# BRK7010.net
KiCad netlist of a schematic drawn in Altium Designer
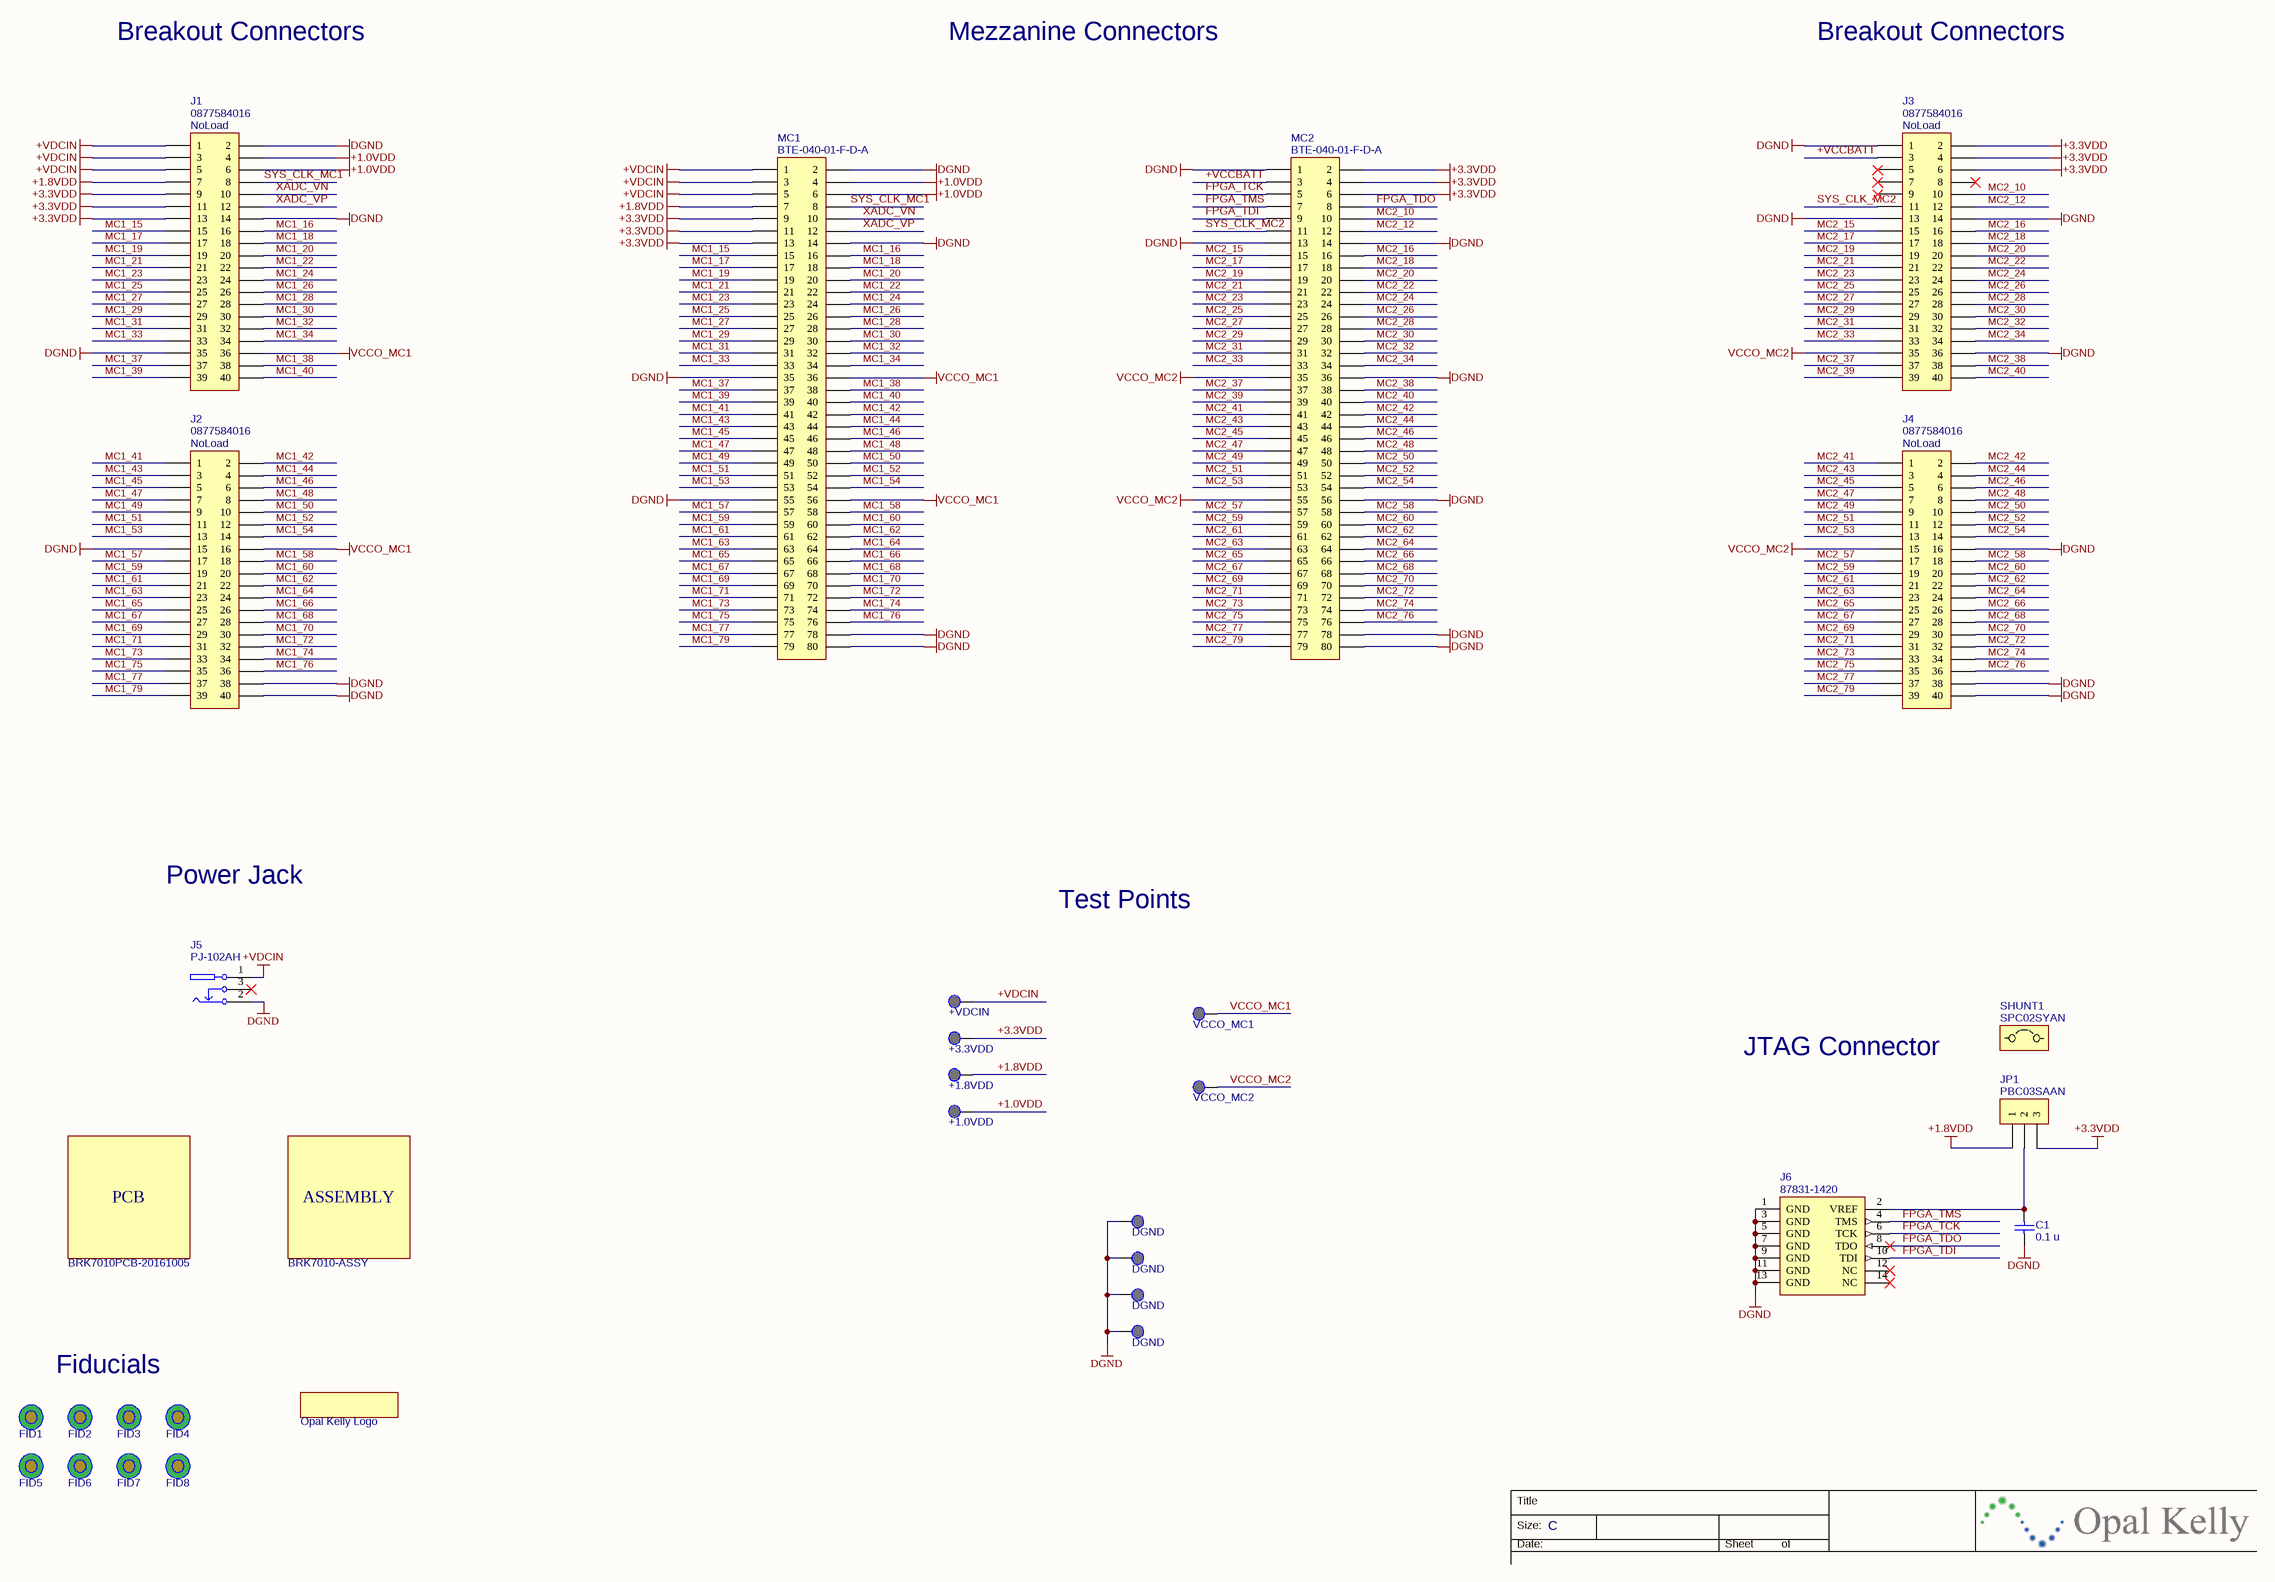
[diagram p0: BRK7010.SchDoc]

(export (version "E")
  (design (tool "Eeschema 10.0.6"))
  (components
    (comp (ref "*1")
      (value "Opal Kelly Logo")
      (footprint "okLogo-23x5")
      (libsource (lib "NoBOM") (part "OKLOGO"))
    )
    (comp (ref "ASSY1")
      (value "BRK7010-ASSY")
      (description "BRK7010 PCB assembly")
      (fields (field (name "MANUFACTURER") "PCB Assembly Cost") (field (name "PARTNUMBER") "001451"))
      (libsource (lib "Aligni") (part "ASSEMBLY"))
    )
    (comp (ref "C1")
      (value "0.1 u")
      (footprint "CAPC1608N")
      (description "Ceramic capacitor")
      (fields (field (name "MANUFACTURER") "Kemet") (field (name "PARTNUMBER") "000019"))
      (libsource (lib "Aligni") (part "Capacitor"))
    )
    (comp (ref "FID1")
      (value "FIDUCIAL")
      (footprint "FID1MM/2MM-SS")
      (description "PCB fiducial")
      (libsource (lib "NoBOM") (part "FIDUCIAL"))
    )
    (comp (ref "FID2")
      (value "FIDUCIAL")
      (footprint "FID1MM/2MM-SS")
      (description "PCB fiducial")
      (libsource (lib "NoBOM") (part "FIDUCIAL"))
    )
    (comp (ref "FID3")
      (value "FIDUCIAL")
      (footprint "FID1MM/2MM-SS")
      (description "PCB fiducial")
      (libsource (lib "NoBOM") (part "FIDUCIAL"))
    )
    (comp (ref "FID4")
      (value "FIDUCIAL")
      (footprint "FID1MM/2MM-SS")
      (description "PCB fiducial")
      (libsource (lib "NoBOM") (part "FIDUCIAL"))
    )
    (comp (ref "FID5")
      (value "FIDUCIAL")
      (footprint "FID1MM/2MM-SS")
      (description "PCB fiducial")
      (libsource (lib "NoBOM") (part "FIDUCIAL"))
    )
    (comp (ref "FID6")
      (value "FIDUCIAL")
      (footprint "FID1MM/2MM-SS")
      (description "PCB fiducial")
      (libsource (lib "NoBOM") (part "FIDUCIAL"))
    )
    (comp (ref "FID7")
      (value "FIDUCIAL")
      (footprint "FID1MM/2MM-SS")
      (description "PCB fiducial")
      (libsource (lib "NoBOM") (part "FIDUCIAL"))
    )
    (comp (ref "FID8")
      (value "FIDUCIAL")
      (footprint "FID1MM/2MM-SS")
      (description "PCB fiducial")
      (libsource (lib "NoBOM") (part "FIDUCIAL"))
    )
    (comp (ref "J1")
      (value "0877584016")
      (footprint "HDR2X20-2MM")
      (description "2mm header, 20x2, thru-hole")
      (fields
        (field (name "MANUFACTURER") "Molex")
        (field (name "PARTNUMBER") "000583")
        (field (name "NOLOAD") "NoLoad")
      )
      (libsource (lib "Aligni") (part "Header 20X2"))
    )
    (comp (ref "J2")
      (value "0877584016")
      (footprint "HDR2X20-2MM")
      (description "2mm header, 20x2, thru-hole")
      (fields
        (field (name "MANUFACTURER") "Molex")
        (field (name "PARTNUMBER") "000583")
        (field (name "NOLOAD") "NoLoad")
      )
      (libsource (lib "Aligni") (part "Header 20X2"))
    )
    (comp (ref "J3")
      (value "0877584016")
      (footprint "HDR2X20-2MM")
      (description "2mm header, 20x2, thru-hole")
      (fields
        (field (name "MANUFACTURER") "Molex")
        (field (name "PARTNUMBER") "000583")
        (field (name "NOLOAD") "NoLoad")
      )
      (libsource (lib "Aligni") (part "Header 20X2"))
    )
    (comp (ref "J4")
      (value "0877584016")
      (footprint "HDR2X20-2MM")
      (description "2mm header, 20x2, thru-hole")
      (fields
        (field (name "MANUFACTURER") "Molex")
        (field (name "PARTNUMBER") "000583")
        (field (name "NOLOAD") "NoLoad")
      )
      (libsource (lib "Aligni") (part "Header 20X2"))
    )
    (comp (ref "J5")
      (value "PJ-102AH")
      (footprint "CUI-PJ102A")
      (description "DC power connector - high current")
      (fields (field (name "MANUFACTURER") "CUI Inc.") (field (name "PARTNUMBER") "000356"))
      (libsource (lib "Aligni") (part "DCPOWER"))
    )
    (comp (ref "J6")
      (value "87831-1420")
      (footprint "HDR2X7-2MM")
      (description "2mm header, shrouded")
      (fields (field (name "MANUFACTURER") "Molex") (field (name "PARTNUMBER") "000541"))
      (libsource (lib "Aligni") (part "JTAGXLNX"))
    )
    (comp (ref "JP1")
      (value "PBC03SAAN")
      (footprint "HDR1X3")
      (description "Single-row header")
      (fields (field (name "MANUFACTURER") "Sullins Electronics Corp.") (field (name "PARTNUMBER") "001173"))
      (libsource (lib "Aligni") (part "Header 1X3"))
    )
    (comp (ref "MC1")
      (value "BTE-040-01-F-D-A")
      (footprint "BTE-040")
      (description "0.8mm high-density header")
      (fields (field (name "MANUFACTURER") "Samtec") (field (name "PARTNUMBER") "000059"))
      (libsource (lib "Aligni") (part "BTE_BSE-040"))
    )
    (comp (ref "MC2")
      (value "BTE-040-01-F-D-A")
      (footprint "BTE-040")
      (description "0.8mm high-density header")
      (fields (field (name "MANUFACTURER") "Samtec") (field (name "PARTNUMBER") "000059"))
      (libsource (lib "Aligni") (part "BTE_BSE-040"))
    )
    (comp (ref "PCB1")
      (value "BRK7010PCB-20161005")
      (description "PCB for BRK7010")
      (fields (field (name "MANUFACTURER") "Generic PCB Manufacturer") (field (name "PARTNUMBER") "001452"))
      (libsource (lib "Aligni") (part "PCB"))
    )
    (comp (ref "SHUNT1")
      (value "SPC02SYAN")
      (description "0.1\" shunt")
      (fields (field (name "MANUFACTURER") "Sullins Electronics Corp.") (field (name "PARTNUMBER") "000078"))
      (libsource (lib "Aligni") (part "Shunt"))
    )
    (comp (ref "TP1")
      (value "+VDCIN")
      (footprint "TP-PTH-65/100")
      (description "Test point, plated through-hole, 65/100mil")
      (libsource (lib "NoBOM") (part "TP-PTH-65/100"))
    )
    (comp (ref "TP2")
      (value "VCCO_MC1")
      (footprint "TP-PTH-65/100")
      (description "Test point, plated through-hole, 65/100mil")
      (libsource (lib "NoBOM") (part "TP-PTH-65/100"))
    )
    (comp (ref "TP3")
      (value "+3.3VDD")
      (footprint "TP-PTH-65/100")
      (description "Test point, plated through-hole, 65/100mil")
      (libsource (lib "NoBOM") (part "TP-PTH-65/100"))
    )
    (comp (ref "TP4")
      (value "+1.8VDD")
      (footprint "TP-PTH-65/100")
      (description "Test point, plated through-hole, 65/100mil")
      (libsource (lib "NoBOM") (part "TP-PTH-65/100"))
    )
    (comp (ref "TP5")
      (value "VCCO_MC2")
      (footprint "TP-PTH-65/100")
      (description "Test point, plated through-hole, 65/100mil")
      (libsource (lib "NoBOM") (part "TP-PTH-65/100"))
    )
    (comp (ref "TP6")
      (value "+1.0VDD")
      (footprint "TP-PTH-65/100")
      (description "Test point, plated through-hole, 65/100mil")
      (libsource (lib "NoBOM") (part "TP-PTH-65/100"))
    )
    (comp (ref "TP7")
      (value "DGND")
      (footprint "TP-PTH-65/100")
      (description "Test point, plated through-hole, 65/100mil")
      (libsource (lib "NoBOM") (part "TP-PTH-65/100"))
    )
    (comp (ref "TP8")
      (value "DGND")
      (footprint "TP-PTH-65/100")
      (description "Test point, plated through-hole, 65/100mil")
      (libsource (lib "NoBOM") (part "TP-PTH-65/100"))
    )
    (comp (ref "TP9")
      (value "DGND")
      (footprint "TP-PTH-65/100")
      (description "Test point, plated through-hole, 65/100mil")
      (libsource (lib "NoBOM") (part "TP-PTH-65/100"))
    )
    (comp (ref "TP10")
      (value "DGND")
      (footprint "TP-PTH-65/100")
      (description "Test point, plated through-hole, 65/100mil")
      (libsource (lib "NoBOM") (part "TP-PTH-65/100"))
    )
  )
  (nets
    (net (code "1") (name "+1.0VDD") (class "Default")
      (node (ref "J1") (pin "4") (pinfunction "4_4") (pintype "passive"))
      (node (ref "J1") (pin "6") (pinfunction "6_6") (pintype "passive"))
      (node (ref "MC1") (pin "4") (pinfunction "4_4") (pintype "passive"))
      (node (ref "MC1") (pin "6") (pinfunction "6_6") (pintype "passive"))
      (node (ref "TP6") (pin "1") (pinfunction "PIN_1") (pintype "passive"))
    )
    (net (code "2") (name "+1.8VDD") (class "Default")
      (node (ref "J1") (pin "7") (pinfunction "7_7") (pintype "passive"))
      (node (ref "JP1") (pin "1") (pinfunction "1_1") (pintype "passive"))
      (node (ref "MC1") (pin "7") (pinfunction "7_7") (pintype "passive"))
      (node (ref "TP4") (pin "1") (pinfunction "PIN_1") (pintype "passive"))
    )
    (net (code "3") (name "+3.3VDD") (class "Default")
      (node (ref "J1") (pin "11") (pinfunction "11_11") (pintype "passive"))
      (node (ref "J1") (pin "13") (pinfunction "13_13") (pintype "passive"))
      (node (ref "J1") (pin "9") (pinfunction "9_9") (pintype "passive"))
      (node (ref "J3") (pin "2") (pinfunction "2_2") (pintype "passive"))
      (node (ref "J3") (pin "4") (pinfunction "4_4") (pintype "passive"))
      (node (ref "J3") (pin "6") (pinfunction "6_6") (pintype "passive"))
      (node (ref "JP1") (pin "3") (pinfunction "3_3") (pintype "passive"))
      (node (ref "MC1") (pin "11") (pinfunction "11_11") (pintype "passive"))
      (node (ref "MC1") (pin "13") (pinfunction "13_13") (pintype "passive"))
      (node (ref "MC1") (pin "9") (pinfunction "9_9") (pintype "passive"))
      (node (ref "MC2") (pin "2") (pinfunction "2_2") (pintype "passive"))
      (node (ref "MC2") (pin "4") (pinfunction "4_4") (pintype "passive"))
      (node (ref "MC2") (pin "6") (pinfunction "6_6") (pintype "passive"))
      (node (ref "TP3") (pin "1") (pinfunction "PIN_1") (pintype "passive"))
    )
    (net (code "4") (name "+VDCIN") (class "Default")
      (node (ref "J1") (pin "1") (pinfunction "1_1") (pintype "passive"))
      (node (ref "J1") (pin "3") (pinfunction "3_3") (pintype "passive"))
      (node (ref "J1") (pin "5") (pinfunction "5_5") (pintype "passive"))
      (node (ref "J5") (pin "1") (pinfunction "1_1") (pintype "passive"))
      (node (ref "MC1") (pin "1") (pinfunction "1_1") (pintype "passive"))
      (node (ref "MC1") (pin "3") (pinfunction "3_3") (pintype "passive"))
      (node (ref "MC1") (pin "5") (pinfunction "5_5") (pintype "passive"))
      (node (ref "TP1") (pin "1") (pinfunction "PIN_1") (pintype "passive"))
    )
    (net (code "5") (name "/+VCCBATT") (class "Default")
      (node (ref "J3") (pin "3") (pinfunction "3_3") (pintype "passive"))
      (node (ref "MC2") (pin "3") (pinfunction "3_3") (pintype "passive"))
    )
    (net (code "6") (name "/FPGA_TCK") (class "Default")
      (node (ref "J6") (pin "6") (pinfunction "TCK_6") (pintype "output"))
      (node (ref "MC2") (pin "5") (pinfunction "5_5") (pintype "passive"))
    )
    (net (code "7") (name "/FPGA_TDI") (class "Default")
      (node (ref "J6") (pin "10") (pinfunction "TDI_10") (pintype "output"))
      (node (ref "MC2") (pin "9") (pinfunction "9_9") (pintype "passive"))
    )
    (net (code "8") (name "/FPGA_TDO") (class "Default")
      (node (ref "J6") (pin "8") (pinfunction "TDO_8") (pintype "input"))
      (node (ref "MC2") (pin "8") (pinfunction "8_8") (pintype "passive"))
    )
    (net (code "9") (name "/FPGA_TMS") (class "Default")
      (node (ref "J6") (pin "4") (pinfunction "TMS_4") (pintype "output"))
      (node (ref "MC2") (pin "7") (pinfunction "7_7") (pintype "passive"))
    )
    (net (code "10") (name "/MC1_15") (class "Default")
      (node (ref "J1") (pin "15") (pinfunction "15_15") (pintype "passive"))
      (node (ref "MC1") (pin "15") (pinfunction "15_15") (pintype "passive"))
    )
    (net (code "11") (name "/MC1_16") (class "Default")
      (node (ref "J1") (pin "16") (pinfunction "16_16") (pintype "passive"))
      (node (ref "MC1") (pin "16") (pinfunction "16_16") (pintype "passive"))
    )
    (net (code "12") (name "/MC1_17") (class "Default")
      (node (ref "J1") (pin "17") (pinfunction "17_17") (pintype "passive"))
      (node (ref "MC1") (pin "17") (pinfunction "17_17") (pintype "passive"))
    )
    (net (code "13") (name "/MC1_18") (class "Default")
      (node (ref "J1") (pin "18") (pinfunction "18_18") (pintype "passive"))
      (node (ref "MC1") (pin "18") (pinfunction "18_18") (pintype "passive"))
    )
    (net (code "14") (name "/MC1_19") (class "Default")
      (node (ref "J1") (pin "19") (pinfunction "19_19") (pintype "passive"))
      (node (ref "MC1") (pin "19") (pinfunction "19_19") (pintype "passive"))
    )
    (net (code "15") (name "/MC1_20") (class "Default")
      (node (ref "J1") (pin "20") (pinfunction "20_20") (pintype "passive"))
      (node (ref "MC1") (pin "20") (pinfunction "20_20") (pintype "passive"))
    )
    (net (code "16") (name "/MC1_21") (class "Default")
      (node (ref "J1") (pin "21") (pinfunction "21_21") (pintype "passive"))
      (node (ref "MC1") (pin "21") (pinfunction "21_21") (pintype "passive"))
    )
    (net (code "17") (name "/MC1_22") (class "Default")
      (node (ref "J1") (pin "22") (pinfunction "22_22") (pintype "passive"))
      (node (ref "MC1") (pin "22") (pinfunction "22_22") (pintype "passive"))
    )
    (net (code "18") (name "/MC1_23") (class "Default")
      (node (ref "J1") (pin "23") (pinfunction "23_23") (pintype "passive"))
      (node (ref "MC1") (pin "23") (pinfunction "23_23") (pintype "passive"))
    )
    (net (code "19") (name "/MC1_24") (class "Default")
      (node (ref "J1") (pin "24") (pinfunction "24_24") (pintype "passive"))
      (node (ref "MC1") (pin "24") (pinfunction "24_24") (pintype "passive"))
    )
    (net (code "20") (name "/MC1_25") (class "Default")
      (node (ref "J1") (pin "25") (pinfunction "25_25") (pintype "passive"))
      (node (ref "MC1") (pin "25") (pinfunction "25_25") (pintype "passive"))
    )
    (net (code "21") (name "/MC1_26") (class "Default")
      (node (ref "J1") (pin "26") (pinfunction "26_26") (pintype "passive"))
      (node (ref "MC1") (pin "26") (pinfunction "26_26") (pintype "passive"))
    )
    (net (code "22") (name "/MC1_27") (class "Default")
      (node (ref "J1") (pin "27") (pinfunction "27_27") (pintype "passive"))
      (node (ref "MC1") (pin "27") (pinfunction "27_27") (pintype "passive"))
    )
    (net (code "23") (name "/MC1_28") (class "Default")
      (node (ref "J1") (pin "28") (pinfunction "28_28") (pintype "passive"))
      (node (ref "MC1") (pin "28") (pinfunction "28_28") (pintype "passive"))
    )
    (net (code "24") (name "/MC1_29") (class "Default")
      (node (ref "J1") (pin "29") (pinfunction "29_29") (pintype "passive"))
      (node (ref "MC1") (pin "29") (pinfunction "29_29") (pintype "passive"))
    )
    (net (code "25") (name "/MC1_30") (class "Default")
      (node (ref "J1") (pin "30") (pinfunction "30_30") (pintype "passive"))
      (node (ref "MC1") (pin "30") (pinfunction "30_30") (pintype "passive"))
    )
    (net (code "26") (name "/MC1_31") (class "Default")
      (node (ref "J1") (pin "31") (pinfunction "31_31") (pintype "passive"))
      (node (ref "MC1") (pin "31") (pinfunction "31_31") (pintype "passive"))
    )
    (net (code "27") (name "/MC1_32") (class "Default")
      (node (ref "J1") (pin "32") (pinfunction "32_32") (pintype "passive"))
      (node (ref "MC1") (pin "32") (pinfunction "32_32") (pintype "passive"))
    )
    (net (code "28") (name "/MC1_33") (class "Default")
      (node (ref "J1") (pin "33") (pinfunction "33_33") (pintype "passive"))
      (node (ref "MC1") (pin "33") (pinfunction "33_33") (pintype "passive"))
    )
    (net (code "29") (name "/MC1_34") (class "Default")
      (node (ref "J1") (pin "34") (pinfunction "34_34") (pintype "passive"))
      (node (ref "MC1") (pin "34") (pinfunction "34_34") (pintype "passive"))
    )
    (net (code "30") (name "/MC1_37") (class "Default")
      (node (ref "J1") (pin "37") (pinfunction "37_37") (pintype "passive"))
      (node (ref "MC1") (pin "37") (pinfunction "37_37") (pintype "passive"))
    )
    (net (code "31") (name "/MC1_38") (class "Default")
      (node (ref "J1") (pin "38") (pinfunction "38_38") (pintype "passive"))
      (node (ref "MC1") (pin "38") (pinfunction "38_38") (pintype "passive"))
    )
    (net (code "32") (name "/MC1_39") (class "Default")
      (node (ref "J1") (pin "39") (pinfunction "39_39") (pintype "passive"))
      (node (ref "MC1") (pin "39") (pinfunction "39_39") (pintype "passive"))
    )
    (net (code "33") (name "/MC1_40") (class "Default")
      (node (ref "J1") (pin "40") (pinfunction "40_40") (pintype "passive"))
      (node (ref "MC1") (pin "40") (pinfunction "40_40") (pintype "passive"))
    )
    (net (code "34") (name "/MC1_41") (class "Default")
      (node (ref "J2") (pin "1") (pinfunction "1_1") (pintype "passive"))
      (node (ref "MC1") (pin "41") (pinfunction "41_41") (pintype "passive"))
    )
    (net (code "35") (name "/MC1_42") (class "Default")
      (node (ref "J2") (pin "2") (pinfunction "2_2") (pintype "passive"))
      (node (ref "MC1") (pin "42") (pinfunction "42_42") (pintype "passive"))
    )
    (net (code "36") (name "/MC1_43") (class "Default")
      (node (ref "J2") (pin "3") (pinfunction "3_3") (pintype "passive"))
      (node (ref "MC1") (pin "43") (pinfunction "43_43") (pintype "passive"))
    )
    (net (code "37") (name "/MC1_44") (class "Default")
      (node (ref "J2") (pin "4") (pinfunction "4_4") (pintype "passive"))
      (node (ref "MC1") (pin "44") (pinfunction "44_44") (pintype "passive"))
    )
    (net (code "38") (name "/MC1_45") (class "Default")
      (node (ref "J2") (pin "5") (pinfunction "5_5") (pintype "passive"))
      (node (ref "MC1") (pin "45") (pinfunction "45_45") (pintype "passive"))
    )
    (net (code "39") (name "/MC1_46") (class "Default")
      (node (ref "J2") (pin "6") (pinfunction "6_6") (pintype "passive"))
      (node (ref "MC1") (pin "46") (pinfunction "46_46") (pintype "passive"))
    )
    (net (code "40") (name "/MC1_47") (class "Default")
      (node (ref "J2") (pin "7") (pinfunction "7_7") (pintype "passive"))
      (node (ref "MC1") (pin "47") (pinfunction "47_47") (pintype "passive"))
    )
    (net (code "41") (name "/MC1_48") (class "Default")
      (node (ref "J2") (pin "8") (pinfunction "8_8") (pintype "passive"))
      (node (ref "MC1") (pin "48") (pinfunction "48_48") (pintype "passive"))
    )
    (net (code "42") (name "/MC1_49") (class "Default")
      (node (ref "J2") (pin "9") (pinfunction "9_9") (pintype "passive"))
      (node (ref "MC1") (pin "49") (pinfunction "49_49") (pintype "passive"))
    )
    (net (code "43") (name "/MC1_50") (class "Default")
      (node (ref "J2") (pin "10") (pinfunction "10_10") (pintype "passive"))
      (node (ref "MC1") (pin "50") (pinfunction "50_50") (pintype "passive"))
    )
    (net (code "44") (name "/MC1_51") (class "Default")
      (node (ref "J2") (pin "11") (pinfunction "11_11") (pintype "passive"))
      (node (ref "MC1") (pin "51") (pinfunction "51_51") (pintype "passive"))
    )
    (net (code "45") (name "/MC1_52") (class "Default")
      (node (ref "J2") (pin "12") (pinfunction "12_12") (pintype "passive"))
      (node (ref "MC1") (pin "52") (pinfunction "52_52") (pintype "passive"))
    )
    (net (code "46") (name "/MC1_53") (class "Default")
      (node (ref "J2") (pin "13") (pinfunction "13_13") (pintype "passive"))
      (node (ref "MC1") (pin "53") (pinfunction "53_53") (pintype "passive"))
    )
    (net (code "47") (name "/MC1_54") (class "Default")
      (node (ref "J2") (pin "14") (pinfunction "14_14") (pintype "passive"))
      (node (ref "MC1") (pin "54") (pinfunction "54_54") (pintype "passive"))
    )
    (net (code "48") (name "/MC1_57") (class "Default")
      (node (ref "J2") (pin "17") (pinfunction "17_17") (pintype "passive"))
      (node (ref "MC1") (pin "57") (pinfunction "57_57") (pintype "passive"))
    )
    (net (code "49") (name "/MC1_58") (class "Default")
      (node (ref "J2") (pin "18") (pinfunction "18_18") (pintype "passive"))
      (node (ref "MC1") (pin "58") (pinfunction "58_58") (pintype "passive"))
    )
    (net (code "50") (name "/MC1_59") (class "Default")
      (node (ref "J2") (pin "19") (pinfunction "19_19") (pintype "passive"))
      (node (ref "MC1") (pin "59") (pinfunction "59_59") (pintype "passive"))
    )
    (net (code "51") (name "/MC1_60") (class "Default")
      (node (ref "J2") (pin "20") (pinfunction "20_20") (pintype "passive"))
      (node (ref "MC1") (pin "60") (pinfunction "60_60") (pintype "passive"))
    )
    (net (code "52") (name "/MC1_61") (class "Default")
      (node (ref "J2") (pin "21") (pinfunction "21_21") (pintype "passive"))
      (node (ref "MC1") (pin "61") (pinfunction "61_61") (pintype "passive"))
    )
    (net (code "53") (name "/MC1_62") (class "Default")
      (node (ref "J2") (pin "22") (pinfunction "22_22") (pintype "passive"))
      (node (ref "MC1") (pin "62") (pinfunction "62_62") (pintype "passive"))
    )
    (net (code "54") (name "/MC1_63") (class "Default")
      (node (ref "J2") (pin "23") (pinfunction "23_23") (pintype "passive"))
      (node (ref "MC1") (pin "63") (pinfunction "63_63") (pintype "passive"))
    )
    (net (code "55") (name "/MC1_64") (class "Default")
      (node (ref "J2") (pin "24") (pinfunction "24_24") (pintype "passive"))
      (node (ref "MC1") (pin "64") (pinfunction "64_64") (pintype "passive"))
    )
    (net (code "56") (name "/MC1_65") (class "Default")
      (node (ref "J2") (pin "25") (pinfunction "25_25") (pintype "passive"))
      (node (ref "MC1") (pin "65") (pinfunction "65_65") (pintype "passive"))
    )
    (net (code "57") (name "/MC1_66") (class "Default")
      (node (ref "J2") (pin "26") (pinfunction "26_26") (pintype "passive"))
      (node (ref "MC1") (pin "66") (pinfunction "66_66") (pintype "passive"))
    )
    (net (code "58") (name "/MC1_67") (class "Default")
      (node (ref "J2") (pin "27") (pinfunction "27_27") (pintype "passive"))
      (node (ref "MC1") (pin "67") (pinfunction "67_67") (pintype "passive"))
    )
    (net (code "59") (name "/MC1_68") (class "Default")
      (node (ref "J2") (pin "28") (pinfunction "28_28") (pintype "passive"))
      (node (ref "MC1") (pin "68") (pinfunction "68_68") (pintype "passive"))
    )
    (net (code "60") (name "/MC1_69") (class "Default")
      (node (ref "J2") (pin "29") (pinfunction "29_29") (pintype "passive"))
      (node (ref "MC1") (pin "69") (pinfunction "69_69") (pintype "passive"))
    )
    (net (code "61") (name "/MC1_70") (class "Default")
      (node (ref "J2") (pin "30") (pinfunction "30_30") (pintype "passive"))
      (node (ref "MC1") (pin "70") (pinfunction "70_70") (pintype "passive"))
    )
    (net (code "62") (name "/MC1_71") (class "Default")
      (node (ref "J2") (pin "31") (pinfunction "31_31") (pintype "passive"))
      (node (ref "MC1") (pin "71") (pinfunction "71_71") (pintype "passive"))
    )
    (net (code "63") (name "/MC1_72") (class "Default")
      (node (ref "J2") (pin "32") (pinfunction "32_32") (pintype "passive"))
      (node (ref "MC1") (pin "72") (pinfunction "72_72") (pintype "passive"))
    )
    (net (code "64") (name "/MC1_73") (class "Default")
      (node (ref "J2") (pin "33") (pinfunction "33_33") (pintype "passive"))
      (node (ref "MC1") (pin "73") (pinfunction "73_73") (pintype "passive"))
    )
    (net (code "65") (name "/MC1_74") (class "Default")
      (node (ref "J2") (pin "34") (pinfunction "34_34") (pintype "passive"))
      (node (ref "MC1") (pin "74") (pinfunction "74_74") (pintype "passive"))
    )
    (net (code "66") (name "/MC1_75") (class "Default")
      (node (ref "J2") (pin "35") (pinfunction "35_35") (pintype "passive"))
      (node (ref "MC1") (pin "75") (pinfunction "75_75") (pintype "passive"))
    )
    (net (code "67") (name "/MC1_76") (class "Default")
      (node (ref "J2") (pin "36") (pinfunction "36_36") (pintype "passive"))
      (node (ref "MC1") (pin "76") (pinfunction "76_76") (pintype "passive"))
    )
    (net (code "68") (name "/MC1_77") (class "Default")
      (node (ref "J2") (pin "37") (pinfunction "37_37") (pintype "passive"))
      (node (ref "MC1") (pin "77") (pinfunction "77_77") (pintype "passive"))
    )
    (net (code "69") (name "/MC1_79") (class "Default")
      (node (ref "J2") (pin "39") (pinfunction "39_39") (pintype "passive"))
      (node (ref "MC1") (pin "79") (pinfunction "79_79") (pintype "passive"))
    )
    (net (code "70") (name "/MC2_10") (class "Default")
      (node (ref "J3") (pin "10") (pinfunction "10_10") (pintype "passive"))
      (node (ref "MC2") (pin "10") (pinfunction "10_10") (pintype "passive"))
    )
    (net (code "71") (name "/MC2_12") (class "Default")
      (node (ref "J3") (pin "12") (pinfunction "12_12") (pintype "passive"))
      (node (ref "MC2") (pin "12") (pinfunction "12_12") (pintype "passive"))
    )
    (net (code "72") (name "/MC2_15") (class "Default")
      (node (ref "J3") (pin "15") (pinfunction "15_15") (pintype "passive"))
      (node (ref "MC2") (pin "15") (pinfunction "15_15") (pintype "passive"))
    )
    (net (code "73") (name "/MC2_16") (class "Default")
      (node (ref "J3") (pin "16") (pinfunction "16_16") (pintype "passive"))
      (node (ref "MC2") (pin "16") (pinfunction "16_16") (pintype "passive"))
    )
    (net (code "74") (name "/MC2_17") (class "Default")
      (node (ref "J3") (pin "17") (pinfunction "17_17") (pintype "passive"))
      (node (ref "MC2") (pin "17") (pinfunction "17_17") (pintype "passive"))
    )
    (net (code "75") (name "/MC2_18") (class "Default")
      (node (ref "J3") (pin "18") (pinfunction "18_18") (pintype "passive"))
      (node (ref "MC2") (pin "18") (pinfunction "18_18") (pintype "passive"))
    )
    (net (code "76") (name "/MC2_19") (class "Default")
      (node (ref "J3") (pin "19") (pinfunction "19_19") (pintype "passive"))
      (node (ref "MC2") (pin "19") (pinfunction "19_19") (pintype "passive"))
    )
    (net (code "77") (name "/MC2_20") (class "Default")
      (node (ref "J3") (pin "20") (pinfunction "20_20") (pintype "passive"))
      (node (ref "MC2") (pin "20") (pinfunction "20_20") (pintype "passive"))
    )
    (net (code "78") (name "/MC2_21") (class "Default")
      (node (ref "J3") (pin "21") (pinfunction "21_21") (pintype "passive"))
      (node (ref "MC2") (pin "21") (pinfunction "21_21") (pintype "passive"))
    )
    (net (code "79") (name "/MC2_22") (class "Default")
      (node (ref "J3") (pin "22") (pinfunction "22_22") (pintype "passive"))
      (node (ref "MC2") (pin "22") (pinfunction "22_22") (pintype "passive"))
    )
    (net (code "80") (name "/MC2_23") (class "Default")
      (node (ref "J3") (pin "23") (pinfunction "23_23") (pintype "passive"))
      (node (ref "MC2") (pin "23") (pinfunction "23_23") (pintype "passive"))
    )
    (net (code "81") (name "/MC2_24") (class "Default")
      (node (ref "J3") (pin "24") (pinfunction "24_24") (pintype "passive"))
      (node (ref "MC2") (pin "24") (pinfunction "24_24") (pintype "passive"))
    )
    (net (code "82") (name "/MC2_25") (class "Default")
      (node (ref "J3") (pin "25") (pinfunction "25_25") (pintype "passive"))
      (node (ref "MC2") (pin "25") (pinfunction "25_25") (pintype "passive"))
    )
    (net (code "83") (name "/MC2_26") (class "Default")
      (node (ref "J3") (pin "26") (pinfunction "26_26") (pintype "passive"))
      (node (ref "MC2") (pin "26") (pinfunction "26_26") (pintype "passive"))
    )
    (net (code "84") (name "/MC2_27") (class "Default")
      (node (ref "J3") (pin "27") (pinfunction "27_27") (pintype "passive"))
      (node (ref "MC2") (pin "27") (pinfunction "27_27") (pintype "passive"))
    )
    (net (code "85") (name "/MC2_28") (class "Default")
      (node (ref "J3") (pin "28") (pinfunction "28_28") (pintype "passive"))
      (node (ref "MC2") (pin "28") (pinfunction "28_28") (pintype "passive"))
    )
    (net (code "86") (name "/MC2_29") (class "Default")
      (node (ref "J3") (pin "29") (pinfunction "29_29") (pintype "passive"))
      (node (ref "MC2") (pin "29") (pinfunction "29_29") (pintype "passive"))
    )
    (net (code "87") (name "/MC2_30") (class "Default")
      (node (ref "J3") (pin "30") (pinfunction "30_30") (pintype "passive"))
      (node (ref "MC2") (pin "30") (pinfunction "30_30") (pintype "passive"))
    )
    (net (code "88") (name "/MC2_31") (class "Default")
      (node (ref "J3") (pin "31") (pinfunction "31_31") (pintype "passive"))
      (node (ref "MC2") (pin "31") (pinfunction "31_31") (pintype "passive"))
    )
    (net (code "89") (name "/MC2_32") (class "Default")
      (node (ref "J3") (pin "32") (pinfunction "32_32") (pintype "passive"))
      (node (ref "MC2") (pin "32") (pinfunction "32_32") (pintype "passive"))
    )
    (net (code "90") (name "/MC2_33") (class "Default")
      (node (ref "J3") (pin "33") (pinfunction "33_33") (pintype "passive"))
      (node (ref "MC2") (pin "33") (pinfunction "33_33") (pintype "passive"))
    )
    (net (code "91") (name "/MC2_34") (class "Default")
      (node (ref "J3") (pin "34") (pinfunction "34_34") (pintype "passive"))
      (node (ref "MC2") (pin "34") (pinfunction "34_34") (pintype "passive"))
    )
    (net (code "92") (name "/MC2_37") (class "Default")
      (node (ref "J3") (pin "37") (pinfunction "37_37") (pintype "passive"))
      (node (ref "MC2") (pin "37") (pinfunction "37_37") (pintype "passive"))
    )
    (net (code "93") (name "/MC2_38") (class "Default")
      (node (ref "J3") (pin "38") (pinfunction "38_38") (pintype "passive"))
      (node (ref "MC2") (pin "38") (pinfunction "38_38") (pintype "passive"))
    )
    (net (code "94") (name "/MC2_39") (class "Default")
      (node (ref "J3") (pin "39") (pinfunction "39_39") (pintype "passive"))
      (node (ref "MC2") (pin "39") (pinfunction "39_39") (pintype "passive"))
    )
    (net (code "95") (name "/MC2_40") (class "Default")
      (node (ref "J3") (pin "40") (pinfunction "40_40") (pintype "passive"))
      (node (ref "MC2") (pin "40") (pinfunction "40_40") (pintype "passive"))
    )
    (net (code "96") (name "/MC2_41") (class "Default")
      (node (ref "J4") (pin "1") (pinfunction "1_1") (pintype "passive"))
      (node (ref "MC2") (pin "41") (pinfunction "41_41") (pintype "passive"))
    )
    (net (code "97") (name "/MC2_42") (class "Default")
      (node (ref "J4") (pin "2") (pinfunction "2_2") (pintype "passive"))
      (node (ref "MC2") (pin "42") (pinfunction "42_42") (pintype "passive"))
    )
    (net (code "98") (name "/MC2_43") (class "Default")
      (node (ref "J4") (pin "3") (pinfunction "3_3") (pintype "passive"))
      (node (ref "MC2") (pin "43") (pinfunction "43_43") (pintype "passive"))
    )
    (net (code "99") (name "/MC2_44") (class "Default")
      (node (ref "J4") (pin "4") (pinfunction "4_4") (pintype "passive"))
      (node (ref "MC2") (pin "44") (pinfunction "44_44") (pintype "passive"))
    )
    (net (code "100") (name "/MC2_45") (class "Default")
      (node (ref "J4") (pin "5") (pinfunction "5_5") (pintype "passive"))
      (node (ref "MC2") (pin "45") (pinfunction "45_45") (pintype "passive"))
    )
    (net (code "101") (name "/MC2_46") (class "Default")
      (node (ref "J4") (pin "6") (pinfunction "6_6") (pintype "passive"))
      (node (ref "MC2") (pin "46") (pinfunction "46_46") (pintype "passive"))
    )
    (net (code "102") (name "/MC2_47") (class "Default")
      (node (ref "J4") (pin "7") (pinfunction "7_7") (pintype "passive"))
      (node (ref "MC2") (pin "47") (pinfunction "47_47") (pintype "passive"))
    )
    (net (code "103") (name "/MC2_48") (class "Default")
      (node (ref "J4") (pin "8") (pinfunction "8_8") (pintype "passive"))
      (node (ref "MC2") (pin "48") (pinfunction "48_48") (pintype "passive"))
    )
    (net (code "104") (name "/MC2_49") (class "Default")
      (node (ref "J4") (pin "9") (pinfunction "9_9") (pintype "passive"))
      (node (ref "MC2") (pin "49") (pinfunction "49_49") (pintype "passive"))
    )
    (net (code "105") (name "/MC2_50") (class "Default")
      (node (ref "J4") (pin "10") (pinfunction "10_10") (pintype "passive"))
      (node (ref "MC2") (pin "50") (pinfunction "50_50") (pintype "passive"))
    )
    (net (code "106") (name "/MC2_51") (class "Default")
      (node (ref "J4") (pin "11") (pinfunction "11_11") (pintype "passive"))
      (node (ref "MC2") (pin "51") (pinfunction "51_51") (pintype "passive"))
    )
    (net (code "107") (name "/MC2_52") (class "Default")
      (node (ref "J4") (pin "12") (pinfunction "12_12") (pintype "passive"))
      (node (ref "MC2") (pin "52") (pinfunction "52_52") (pintype "passive"))
    )
    (net (code "108") (name "/MC2_53") (class "Default")
      (node (ref "J4") (pin "13") (pinfunction "13_13") (pintype "passive"))
      (node (ref "MC2") (pin "53") (pinfunction "53_53") (pintype "passive"))
    )
    (net (code "109") (name "/MC2_54") (class "Default")
      (node (ref "J4") (pin "14") (pinfunction "14_14") (pintype "passive"))
      (node (ref "MC2") (pin "54") (pinfunction "54_54") (pintype "passive"))
    )
    (net (code "110") (name "/MC2_57") (class "Default")
      (node (ref "J4") (pin "17") (pinfunction "17_17") (pintype "passive"))
      (node (ref "MC2") (pin "57") (pinfunction "57_57") (pintype "passive"))
    )
    (net (code "111") (name "/MC2_58") (class "Default")
      (node (ref "J4") (pin "18") (pinfunction "18_18") (pintype "passive"))
      (node (ref "MC2") (pin "58") (pinfunction "58_58") (pintype "passive"))
    )
    (net (code "112") (name "/MC2_59") (class "Default")
      (node (ref "J4") (pin "19") (pinfunction "19_19") (pintype "passive"))
      (node (ref "MC2") (pin "59") (pinfunction "59_59") (pintype "passive"))
    )
    (net (code "113") (name "/MC2_60") (class "Default")
      (node (ref "J4") (pin "20") (pinfunction "20_20") (pintype "passive"))
      (node (ref "MC2") (pin "60") (pinfunction "60_60") (pintype "passive"))
    )
    (net (code "114") (name "/MC2_61") (class "Default")
      (node (ref "J4") (pin "21") (pinfunction "21_21") (pintype "passive"))
      (node (ref "MC2") (pin "61") (pinfunction "61_61") (pintype "passive"))
    )
    (net (code "115") (name "/MC2_62") (class "Default")
      (node (ref "J4") (pin "22") (pinfunction "22_22") (pintype "passive"))
      (node (ref "MC2") (pin "62") (pinfunction "62_62") (pintype "passive"))
    )
    (net (code "116") (name "/MC2_63") (class "Default")
      (node (ref "J4") (pin "23") (pinfunction "23_23") (pintype "passive"))
      (node (ref "MC2") (pin "63") (pinfunction "63_63") (pintype "passive"))
    )
    (net (code "117") (name "/MC2_64") (class "Default")
      (node (ref "J4") (pin "24") (pinfunction "24_24") (pintype "passive"))
      (node (ref "MC2") (pin "64") (pinfunction "64_64") (pintype "passive"))
    )
    (net (code "118") (name "/MC2_65") (class "Default")
      (node (ref "J4") (pin "25") (pinfunction "25_25") (pintype "passive"))
      (node (ref "MC2") (pin "65") (pinfunction "65_65") (pintype "passive"))
    )
    (net (code "119") (name "/MC2_66") (class "Default")
      (node (ref "J4") (pin "26") (pinfunction "26_26") (pintype "passive"))
      (node (ref "MC2") (pin "66") (pinfunction "66_66") (pintype "passive"))
    )
    (net (code "120") (name "/MC2_67") (class "Default")
      (node (ref "J4") (pin "27") (pinfunction "27_27") (pintype "passive"))
      (node (ref "MC2") (pin "67") (pinfunction "67_67") (pintype "passive"))
    )
    (net (code "121") (name "/MC2_68") (class "Default")
      (node (ref "J4") (pin "28") (pinfunction "28_28") (pintype "passive"))
      (node (ref "MC2") (pin "68") (pinfunction "68_68") (pintype "passive"))
    )
    (net (code "122") (name "/MC2_69") (class "Default")
      (node (ref "J4") (pin "29") (pinfunction "29_29") (pintype "passive"))
      (node (ref "MC2") (pin "69") (pinfunction "69_69") (pintype "passive"))
    )
    (net (code "123") (name "/MC2_70") (class "Default")
      (node (ref "J4") (pin "30") (pinfunction "30_30") (pintype "passive"))
      (node (ref "MC2") (pin "70") (pinfunction "70_70") (pintype "passive"))
    )
    (net (code "124") (name "/MC2_71") (class "Default")
      (node (ref "J4") (pin "31") (pinfunction "31_31") (pintype "passive"))
      (node (ref "MC2") (pin "71") (pinfunction "71_71") (pintype "passive"))
    )
    (net (code "125") (name "/MC2_72") (class "Default")
      (node (ref "J4") (pin "32") (pinfunction "32_32") (pintype "passive"))
      (node (ref "MC2") (pin "72") (pinfunction "72_72") (pintype "passive"))
    )
    (net (code "126") (name "/MC2_73") (class "Default")
      (node (ref "J4") (pin "33") (pinfunction "33_33") (pintype "passive"))
      (node (ref "MC2") (pin "73") (pinfunction "73_73") (pintype "passive"))
    )
    (net (code "127") (name "/MC2_74") (class "Default")
      (node (ref "J4") (pin "34") (pinfunction "34_34") (pintype "passive"))
      (node (ref "MC2") (pin "74") (pinfunction "74_74") (pintype "passive"))
    )
    (net (code "128") (name "/MC2_75") (class "Default")
      (node (ref "J4") (pin "35") (pinfunction "35_35") (pintype "passive"))
      (node (ref "MC2") (pin "75") (pinfunction "75_75") (pintype "passive"))
    )
    (net (code "129") (name "/MC2_76") (class "Default")
      (node (ref "J4") (pin "36") (pinfunction "36_36") (pintype "passive"))
      (node (ref "MC2") (pin "76") (pinfunction "76_76") (pintype "passive"))
    )
    (net (code "130") (name "/MC2_77") (class "Default")
      (node (ref "J4") (pin "37") (pinfunction "37_37") (pintype "passive"))
      (node (ref "MC2") (pin "77") (pinfunction "77_77") (pintype "passive"))
    )
    (net (code "131") (name "/MC2_79") (class "Default")
      (node (ref "J4") (pin "39") (pinfunction "39_39") (pintype "passive"))
      (node (ref "MC2") (pin "79") (pinfunction "79_79") (pintype "passive"))
    )
    (net (code "132") (name "/SYS_CLK_MC1") (class "Default")
      (node (ref "J1") (pin "8") (pinfunction "8_8") (pintype "passive"))
      (node (ref "MC1") (pin "8") (pinfunction "8_8") (pintype "passive"))
    )
    (net (code "133") (name "/SYS_CLK_MC2") (class "Default")
      (node (ref "J3") (pin "11") (pinfunction "11_11") (pintype "passive"))
      (node (ref "MC2") (pin "11") (pinfunction "11_11") (pintype "passive"))
    )
    (net (code "134") (name "/XADC_VN") (class "Default")
      (node (ref "J1") (pin "10") (pinfunction "10_10") (pintype "passive"))
      (node (ref "MC1") (pin "10") (pinfunction "10_10") (pintype "passive"))
    )
    (net (code "135") (name "/XADC_VP") (class "Default")
      (node (ref "J1") (pin "12") (pinfunction "12_12") (pintype "passive"))
      (node (ref "MC1") (pin "12") (pinfunction "12_12") (pintype "passive"))
    )
    (net (code "136") (name "DGND") (class "Default")
      (node (ref "C1") (pin "1") (pinfunction "1_1") (pintype "passive"))
      (node (ref "J1") (pin "14") (pinfunction "14_14") (pintype "passive"))
      (node (ref "J1") (pin "2") (pinfunction "2_2") (pintype "passive"))
      (node (ref "J1") (pin "35") (pinfunction "35_35") (pintype "passive"))
      (node (ref "J2") (pin "15") (pinfunction "15_15") (pintype "passive"))
      (node (ref "J2") (pin "38") (pinfunction "38_38") (pintype "passive"))
      (node (ref "J2") (pin "40") (pinfunction "40_40") (pintype "passive"))
      (node (ref "J3") (pin "1") (pinfunction "1_1") (pintype "passive"))
      (node (ref "J3") (pin "13") (pinfunction "13_13") (pintype "passive"))
      (node (ref "J3") (pin "14") (pinfunction "14_14") (pintype "passive"))
      (node (ref "J3") (pin "36") (pinfunction "36_36") (pintype "passive"))
      (node (ref "J4") (pin "16") (pinfunction "16_16") (pintype "passive"))
      (node (ref "J4") (pin "38") (pinfunction "38_38") (pintype "passive"))
      (node (ref "J4") (pin "40") (pinfunction "40_40") (pintype "passive"))
      (node (ref "J5") (pin "2") (pinfunction "2_2") (pintype "passive"))
      (node (ref "J6") (pin "1") (pinfunction "GND_1") (pintype "power_in"))
      (node (ref "J6") (pin "11") (pinfunction "GND_11") (pintype "power_in"))
      (node (ref "J6") (pin "13") (pinfunction "GND_13") (pintype "power_in"))
      (node (ref "J6") (pin "3") (pinfunction "GND_3") (pintype "power_in"))
      (node (ref "J6") (pin "5") (pinfunction "GND_5") (pintype "power_in"))
      (node (ref "J6") (pin "7") (pinfunction "GND_7") (pintype "power_in"))
      (node (ref "J6") (pin "9") (pinfunction "GND_9") (pintype "power_in"))
      (node (ref "MC1") (pin "14") (pinfunction "14_14") (pintype "passive"))
      (node (ref "MC1") (pin "2") (pinfunction "2_2") (pintype "passive"))
      (node (ref "MC1") (pin "35") (pinfunction "35_35") (pintype "passive"))
      (node (ref "MC1") (pin "55") (pinfunction "55_55") (pintype "passive"))
      (node (ref "MC1") (pin "78") (pinfunction "78_78") (pintype "passive"))
      (node (ref "MC1") (pin "80") (pinfunction "80_80") (pintype "passive"))
      (node (ref "MC2") (pin "1") (pinfunction "1_1") (pintype "passive"))
      (node (ref "MC2") (pin "13") (pinfunction "13_13") (pintype "passive"))
      (node (ref "MC2") (pin "14") (pinfunction "14_14") (pintype "passive"))
      (node (ref "MC2") (pin "36") (pinfunction "36_36") (pintype "passive"))
      (node (ref "MC2") (pin "56") (pinfunction "56_56") (pintype "passive"))
      (node (ref "MC2") (pin "78") (pinfunction "78_78") (pintype "passive"))
      (node (ref "MC2") (pin "80") (pinfunction "80_80") (pintype "passive"))
      (node (ref "TP10") (pin "1") (pinfunction "PIN_1") (pintype "passive"))
      (node (ref "TP7") (pin "1") (pinfunction "PIN_1") (pintype "passive"))
      (node (ref "TP8") (pin "1") (pinfunction "PIN_1") (pintype "passive"))
      (node (ref "TP9") (pin "1") (pinfunction "PIN_1") (pintype "passive"))
    )
    (net (code "137") (name "Net-(J6-VREF)") (class "Default")
      (node (ref "C1") (pin "2") (pinfunction "2_2") (pintype "passive"))
      (node (ref "J6") (pin "2") (pinfunction "VREF_2") (pintype "power_in"))
      (node (ref "JP1") (pin "2") (pinfunction "2_2") (pintype "passive"))
    )
    (net (code "138") (name "VCCO_MC1") (class "Default")
      (node (ref "J1") (pin "36") (pinfunction "36_36") (pintype "passive"))
      (node (ref "J2") (pin "16") (pinfunction "16_16") (pintype "passive"))
      (node (ref "MC1") (pin "36") (pinfunction "36_36") (pintype "passive"))
      (node (ref "MC1") (pin "56") (pinfunction "56_56") (pintype "passive"))
      (node (ref "TP2") (pin "1") (pinfunction "PIN_1") (pintype "passive"))
    )
    (net (code "139") (name "VCCO_MC2") (class "Default")
      (node (ref "J3") (pin "35") (pinfunction "35_35") (pintype "passive"))
      (node (ref "J4") (pin "15") (pinfunction "15_15") (pintype "passive"))
      (node (ref "MC2") (pin "35") (pinfunction "35_35") (pintype "passive"))
      (node (ref "MC2") (pin "55") (pinfunction "55_55") (pintype "passive"))
      (node (ref "TP5") (pin "1") (pinfunction "PIN_1") (pintype "passive"))
    )
    (net (code "140") (name "unconnected-(J3-Pad5)") (class "Default")
      (node (ref "J3") (pin "5") (pinfunction "5_5") (pintype "passive+no_connect"))
    )
    (net (code "141") (name "unconnected-(J3-Pad7)") (class "Default")
      (node (ref "J3") (pin "7") (pinfunction "7_7") (pintype "passive+no_connect"))
    )
    (net (code "142") (name "unconnected-(J3-Pad8)") (class "Default")
      (node (ref "J3") (pin "8") (pinfunction "8_8") (pintype "passive+no_connect"))
    )
    (net (code "143") (name "unconnected-(J3-Pad9)") (class "Default")
      (node (ref "J3") (pin "9") (pinfunction "9_9") (pintype "passive+no_connect"))
    )
    (net (code "144") (name "unconnected-(J5-Pad3)") (class "Default")
      (node (ref "J5") (pin "3") (pinfunction "3_3") (pintype "passive+no_connect"))
    )
    (net (code "145") (name "unconnected-(J6-NC-Pad12)") (class "Default")
      (node (ref "J6") (pin "12") (pinfunction "NC_12") (pintype "passive+no_connect"))
    )
    (net (code "146") (name "unconnected-(J6-NC-Pad14)") (class "Default")
      (node (ref "J6") (pin "14") (pinfunction "NC_14") (pintype "passive+no_connect"))
    )
  )
)
